# LionIRVT-TM4C_Main.net
KiCad netlist of a schematic drawn in Altium Designer
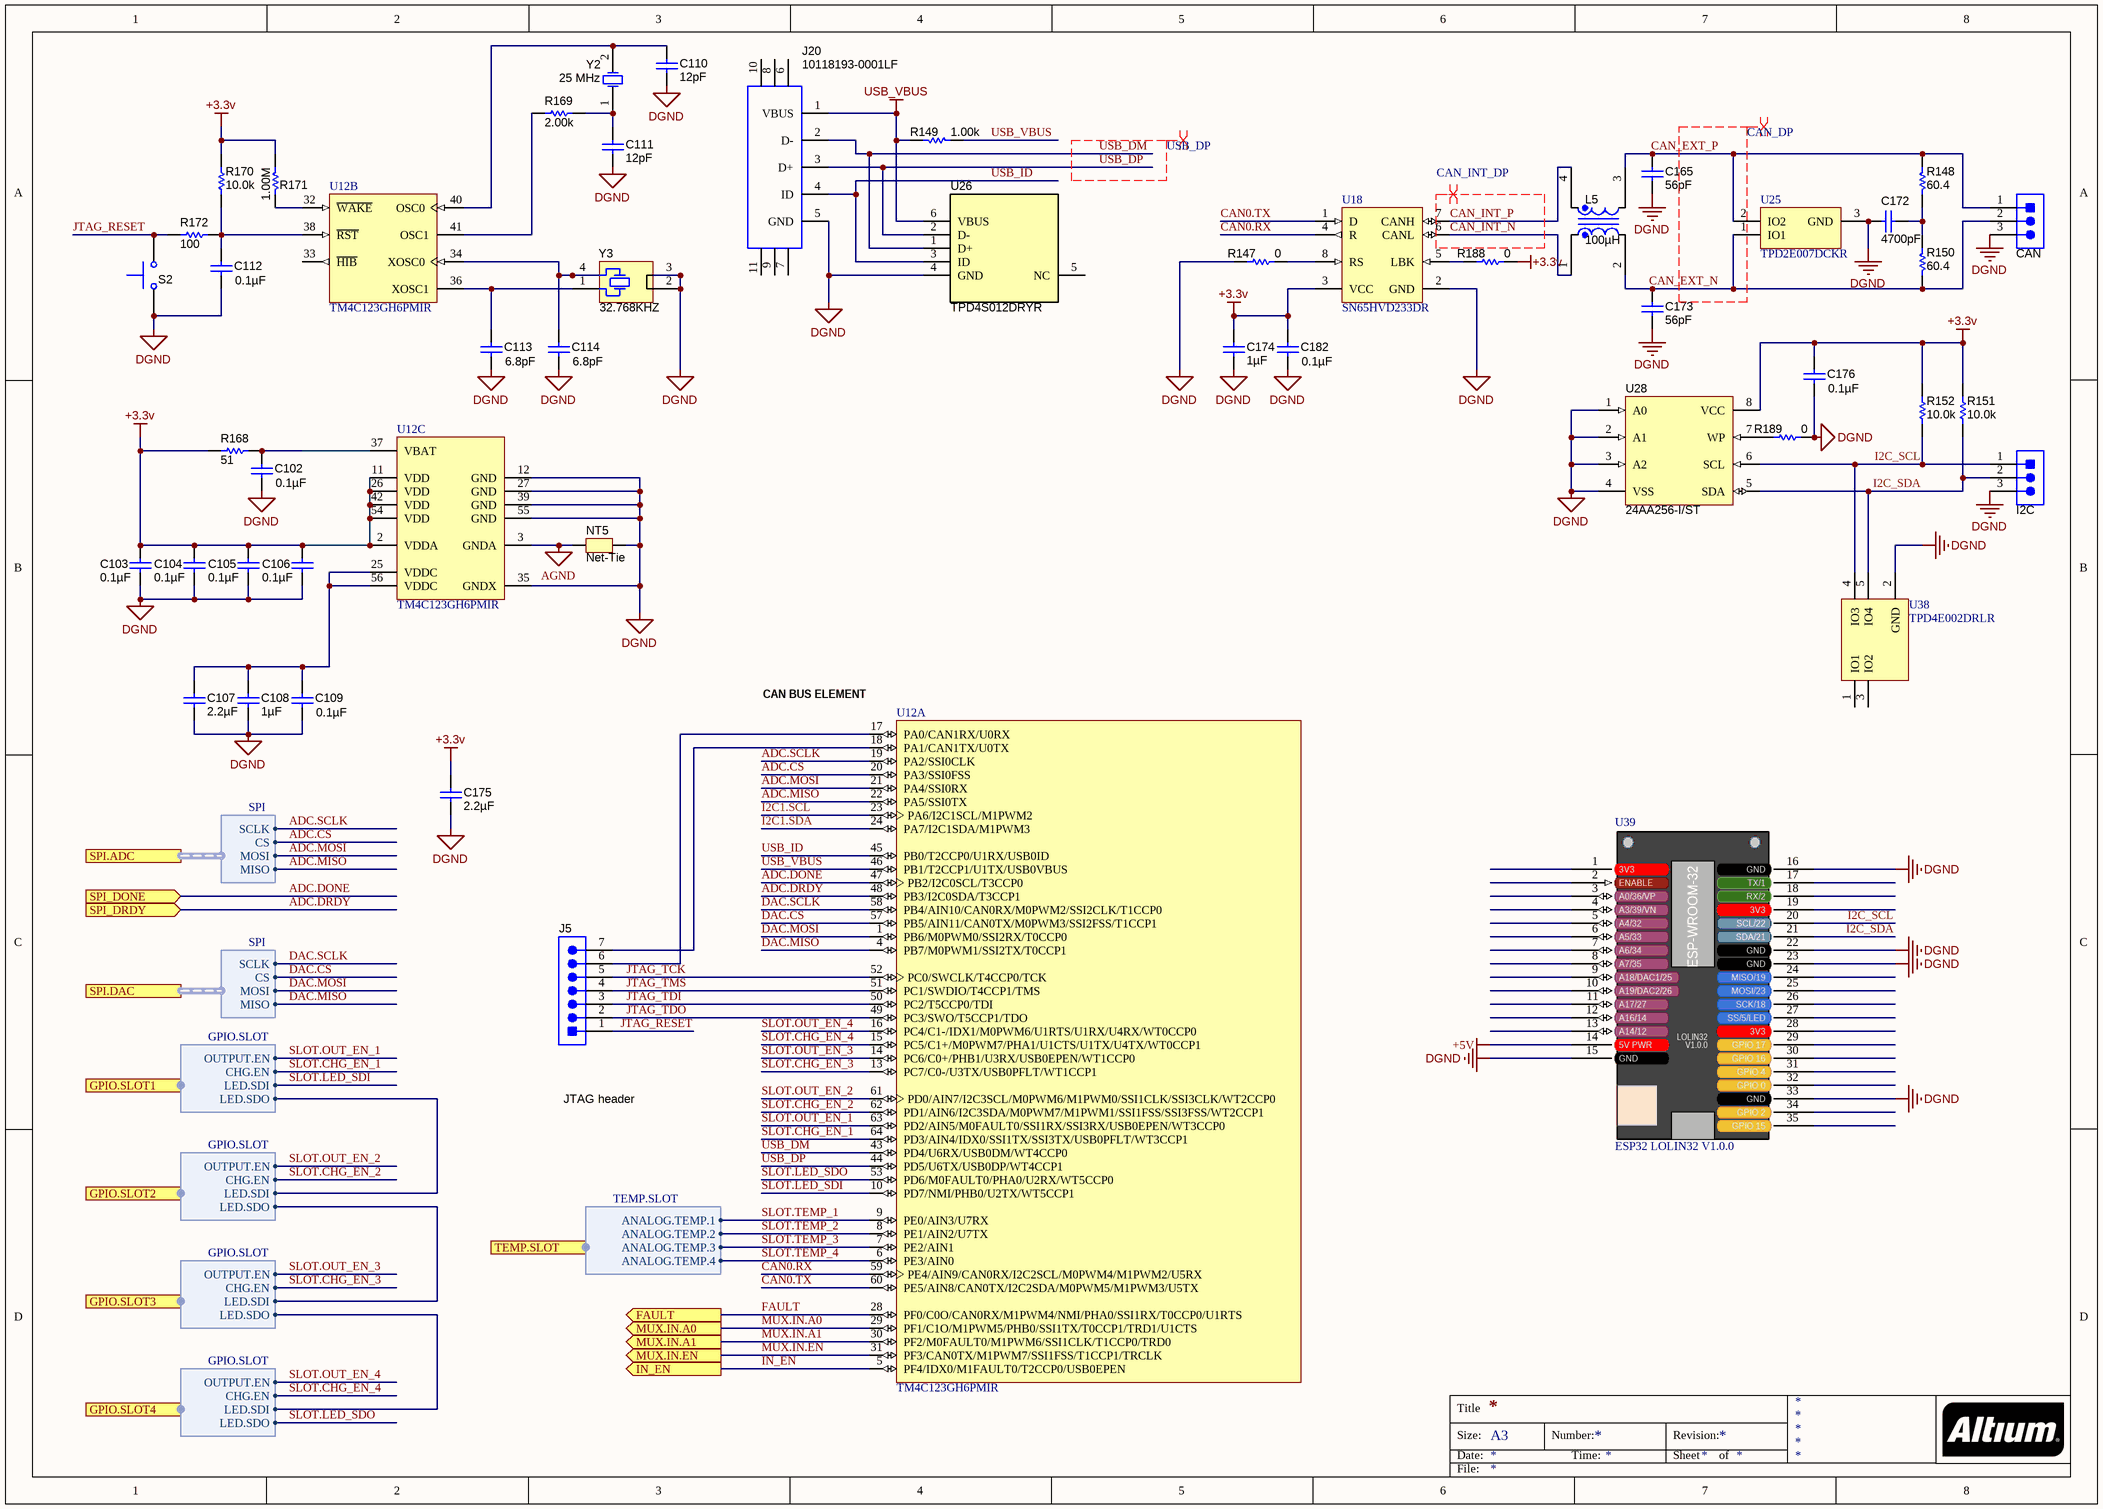
[diagram p0: LionIRVT-TM4C_Main.SchDoc]

(export (version "E")
  (design (tool "Eeschema 10.0.6"))
  (components
    (comp (ref "C102")
      (value "06033C104JAT2A")
      (footprint "0603C")
      (description "CAP, CERM, 0.1 µF, 25 V, +/- 5%, X7R, 0603")
      (fields
        (field (name "VALUEDISPLAYED") "0.1µF")
        (field (name "MANUFACTURER") "AVX")
        (field (name "PUBLISHER") "Texas Instruments")
      )
      (libsource (lib "Capacitor_Ceramic") (part "06033C104JAT2A"))
    )
    (comp (ref "C103")
      (value "06033C104JAT2A")
      (footprint "0603C")
      (description "CAP, CERM, 0.1 µF, 25 V, +/- 5%, X7R, 0603")
      (fields
        (field (name "VALUEDISPLAYED") "0.1µF")
        (field (name "MANUFACTURER") "AVX")
        (field (name "PUBLISHER") "Texas Instruments")
      )
      (libsource (lib "Capacitor_Ceramic") (part "06033C104JAT2A"))
    )
    (comp (ref "C104")
      (value "06033C104JAT2A")
      (footprint "0603C")
      (description "CAP, CERM, 0.1 µF, 25 V, +/- 5%, X7R, 0603")
      (fields
        (field (name "VALUEDISPLAYED") "0.1µF")
        (field (name "MANUFACTURER") "AVX")
        (field (name "PUBLISHER") "Texas Instruments")
      )
      (libsource (lib "Capacitor_Ceramic") (part "06033C104JAT2A"))
    )
    (comp (ref "C105")
      (value "06033C104JAT2A")
      (footprint "0603C")
      (description "CAP, CERM, 0.1 µF, 25 V, +/- 5%, X7R, 0603")
      (fields
        (field (name "VALUEDISPLAYED") "0.1µF")
        (field (name "MANUFACTURER") "AVX")
        (field (name "PUBLISHER") "Texas Instruments")
      )
      (libsource (lib "Capacitor_Ceramic") (part "06033C104JAT2A"))
    )
    (comp (ref "C106")
      (value "06033C104JAT2A")
      (footprint "0603C")
      (description "CAP, CERM, 0.1 µF, 25 V, +/- 5%, X7R, 0603")
      (fields
        (field (name "VALUEDISPLAYED") "0.1µF")
        (field (name "MANUFACTURER") "AVX")
        (field (name "PUBLISHER") "Texas Instruments")
      )
      (libsource (lib "Capacitor_Ceramic") (part "06033C104JAT2A"))
    )
    (comp (ref "C107")
      (value "GRM188R6YA225KA12D")
      (footprint "0603C")
      (description "CAP, CERM, 2.2 µF, 35 V, +/- 10%, X5R, 0603")
      (fields
        (field (name "VALUEDISPLAYED") "2.2µF")
        (field (name "MANUFACTURER") "MuRata")
        (field (name "PUBLISHER") "Texas Instruments")
      )
      (libsource (lib "Capacitor_Ceramic") (part "GRM188R6YA225KA12D"))
    )
    (comp (ref "C108")
      (value "GRM188R71E105KA12D")
      (footprint "0603C")
      (description "CAP, CERM, 1 µF, 25 V, +/- 10%, X7R, 0603")
      (fields
        (field (name "VALUEDISPLAYED") "1µF")
        (field (name "MANUFACTURER") "MuRata")
        (field (name "PUBLISHER") "Texas Instruments")
      )
      (libsource (lib "Capacitor_Ceramic") (part "GRM188R71E105KA12D"))
    )
    (comp (ref "C109")
      (value "06033C104JAT2A")
      (footprint "0603C")
      (description "CAP, CERM, 0.1 µF, 25 V, +/- 5%, X7R, 0603")
      (fields
        (field (name "VALUEDISPLAYED") "0.1µF")
        (field (name "MANUFACTURER") "AVX")
        (field (name "PUBLISHER") "Texas Instruments")
      )
      (libsource (lib "Capacitor_Ceramic") (part "06033C104JAT2A"))
    )
    (comp (ref "C110")
      (value "C0603C120J5GACTU")
      (footprint "0603C")
      (description "CAP, CERM, 12 pF, 50 V, +/- 5%, C0G/NP0, 0603")
      (fields
        (field (name "VALUEDISPLAYED") "12pF")
        (field (name "MANUFACTURER") "Kemet")
        (field (name "PUBLISHER") "Texas Instruments")
      )
      (libsource (lib "Capacitor_Ceramic") (part "C0603C120J5GACTU"))
    )
    (comp (ref "C111")
      (value "C0603C120J5GACTU")
      (footprint "0603C")
      (description "CAP, CERM, 12 pF, 50 V, +/- 5%, C0G/NP0, 0603")
      (fields
        (field (name "VALUEDISPLAYED") "12pF")
        (field (name "MANUFACTURER") "Kemet")
        (field (name "PUBLISHER") "Texas Instruments")
      )
      (libsource (lib "Capacitor_Ceramic") (part "C0603C120J5GACTU"))
    )
    (comp (ref "C112")
      (value "06033C104JAT2A")
      (footprint "0603C")
      (description "CAP, CERM, 0.1 µF, 25 V, +/- 5%, X7R, 0603")
      (fields
        (field (name "VALUEDISPLAYED") "0.1µF")
        (field (name "MANUFACTURER") "AVX")
        (field (name "PUBLISHER") "Texas Instruments")
      )
      (libsource (lib "Capacitor_Ceramic") (part "06033C104JAT2A"))
    )
    (comp (ref "C113")
      (value "06035A6R8CAT2A")
      (footprint "0603C")
      (description "CAP, CERM, 6.8 pF, 50 V, +/- 4%, C0G/NP0, 0603")
      (fields
        (field (name "VALUEDISPLAYED") "6.8pF")
        (field (name "MANUFACTURER") "AVX")
        (field (name "PUBLISHER") "Texas Instruments")
      )
      (libsource (lib "Capacitor_Ceramic") (part "06035A6R8CAT2A"))
    )
    (comp (ref "C114")
      (value "06035A6R8CAT2A")
      (footprint "0603C")
      (description "CAP, CERM, 6.8 pF, 50 V, +/- 4%, C0G/NP0, 0603")
      (fields
        (field (name "VALUEDISPLAYED") "6.8pF")
        (field (name "MANUFACTURER") "AVX")
        (field (name "PUBLISHER") "Texas Instruments")
      )
      (libsource (lib "Capacitor_Ceramic") (part "06035A6R8CAT2A"))
    )
    (comp (ref "C165")
      (value "GRM1885C1H560JA01D")
      (footprint "0603C")
      (description "CAP, CERM, 56 pF, 50 V, +/- 5%, C0G/NP0, 0603")
      (fields
        (field (name "VALUEDISPLAYED") "56pF")
        (field (name "MANUFACTURER") "MuRata")
        (field (name "PUBLISHER") "Texas Instruments")
      )
      (libsource (lib "Capacitor_Ceramic") (part "GRM1885C1H560JA01D"))
    )
    (comp (ref "C172")
      (value "GCM188R71H472KA37D")
      (footprint "0603C")
      (description "CAP, CERM, 4700 pF, 50 V, +/- 10%, X7R, AEC-Q200 Grade 1, 0603")
      (fields
        (field (name "VALUEDISPLAYED") "4700pF")
        (field (name "MANUFACTURER") "MuRata")
        (field (name "PUBLISHER") "Texas Instruments")
      )
      (libsource (lib "Capacitor_Ceramic") (part "GCM188R71H472KA37D"))
    )
    (comp (ref "C173")
      (value "GRM1885C1H560JA01D")
      (footprint "0603")
      (description "CAP, CERM, 56 pF, 50 V, +/- 5%, C0G/NP0, 0603")
      (fields
        (field (name "VALUEDISPLAYED") "56pF")
        (field (name "MANUFACTURER") "MuRata")
        (field (name "PUBLISHER") "Texas Instruments")
      )
      (libsource (lib "Capacitor_Ceramic") (part "GRM1885C1H560JA01D"))
    )
    (comp (ref "C174")
      (value "GRM188R71E105KA12D")
      (footprint "0603")
      (description "CAP, CERM, 1 µF, 25 V, +/- 10%, X7R, 0603")
      (fields
        (field (name "VALUEDISPLAYED") "1µF")
        (field (name "MANUFACTURER") "MuRata")
        (field (name "PUBLISHER") "Texas Instruments")
      )
      (libsource (lib "Capacitor_Ceramic") (part "GRM188R71E105KA12D"))
    )
    (comp (ref "C175")
      (value "GRM188R6YA225KA12D")
      (footprint "0603")
      (description "CAP, CERM, 2.2 µF, 35 V, +/- 10%, X5R, 0603")
      (fields
        (field (name "VALUEDISPLAYED") "2.2µF")
        (field (name "MANUFACTURER") "MuRata")
        (field (name "PUBLISHER") "Texas Instruments")
      )
      (libsource (lib "Capacitor_Ceramic") (part "GRM188R6YA225KA12D"))
    )
    (comp (ref "C176")
      (value "06033C104JAT2A")
      (footprint "0603C")
      (description "CAP, CERM, 0.1 µF, 25 V, +/- 5%, X7R, 0603")
      (fields
        (field (name "VALUEDISPLAYED") "0.1µF")
        (field (name "MANUFACTURER") "AVX")
        (field (name "PUBLISHER") "Texas Instruments")
      )
      (libsource (lib "Capacitor_Ceramic") (part "06033C104JAT2A"))
    )
    (comp (ref "C182")
      (value "06033C104JAT2A")
      (footprint "0603C")
      (description "CAP, CERM, 0.1 µF, 25 V, +/- 5%, X7R, 0603")
      (fields
        (field (name "VALUEDISPLAYED") "0.1µF")
        (field (name "MANUFACTURER") "AVX")
        (field (name "PUBLISHER") "Texas Instruments")
      )
      (libsource (lib "Capacitor_Ceramic") (part "06033C104JAT2A"))
    )
    (comp (ref "CAN")
      (value "ED555/3DS")
      (footprint "TERM_BLK_ED555-3DS")
      (description "Terminal Block, 6A, 3.5mm Pitch, 3-Pos, TH")
      (fields
        (field (name "MANUFACTURER") "On-Shore Technology")
        (field (name "SYMBOLCREATOR") "a0412235")
        (field (name "PUBLISHER") "Texas Instruments")
      )
      (libsource (lib "PWR578A") (part "ED555/3DS"))
    )
    (comp (ref "I2C")
      (value "ED555/3DS")
      (footprint "TERM_BLK_ED555-3DS")
      (description "Terminal Block, 6A, 3.5mm Pitch, 3-Pos, TH")
      (fields
        (field (name "MANUFACTURER") "On-Shore Technology")
        (field (name "SYMBOLCREATOR") "a0412235")
        (field (name "PUBLISHER") "Texas Instruments")
      )
      (libsource (lib "PWR578A") (part "ED555/3DS"))
    )
    (comp (ref "J5")
      (value "TSW-107-07-G-S")
      (footprint "TSW-107-07-G-S")
      (description "Header, 100mil, 7x1, Gold, TH")
      (fields
        (field (name "MANUFACTURER") "Samtec")
        (field (name "SYMBOLCREATOR") "a0411947")
        (field (name "PUBLISHER") "Texas Instruments")
      )
      (libsource (lib "Connectors_Samtec") (part "TSW-107-07-G-S"))
    )
    (comp (ref "J20")
      (value "10118193-0001LF")
      (footprint "FCI_10118193-0001LF")
      (description "Connector, Receptacle, USB Micro B, R/A, SMT")
      (fields (field (name "MANUFACTURER") "FCI") (field (name "PUBLISHER") "Texas Instruments"))
      (libsource (lib "SV601272A") (part "CMP-0065029-1"))
    )
    (comp (ref "L5")
      (value "B82789C0104H001")
      (footprint "SIMDAD_1812")
      (description "Coupled inductor, 100 µH, 0.15 A, 1.5 ohm, SMD")
      (fields
        (field (name "VALUEDISPLAYED") "100µH")
        (field (name "MANUFACTURER") "TDK")
        (field (name "SYMBOLCREATOR") "a0412235")
        (field (name "PUBLISHER") "Texas Instruments")
      )
      (libsource (lib "SV601272A") (part "B82789C0104H001"))
    )
    (comp (ref "NT5")
      (value "Net-Tie")
      (footprint "Net-Tie_10mil")
      (description "Single point connection between nets.")
      (fields (field (name "SYMBOLCREATOR") "codlsc") (field (name "PUBLISHER") "Texas Instruments"))
      (libsource (lib "SV601272A") (part "Net-Tie"))
    )
    (comp (ref "R147")
      (value "Resistor")
      (footprint "0603R")
      (description "RES, 0, 5%, 0.1 W, 0603")
      (fields
        (field (name "PARTNUMBER") "ERJ-3GEY0R00V")
        (field (name "MANUFACTURER") "Panasonic")
        (field (name "VALUEDISPLAYED") "0")
        (field (name "PUBLISHER") "Texas Instruments")
      )
      (libsource (lib "PMP40182") (part "Resistor"))
    )
    (comp (ref "R148")
      (value "CRCW120660R4FKEA")
      (footprint "1206R")
      (description "RES, 60.4, 1%, 0.25 W, 1206")
      (fields
        (field (name "VALUEDISPLAYED") "60.4")
        (field (name "MANUFACTURER") "Vishay-Dale")
        (field (name "PUBLISHER") "Texas Instruments")
      )
      (libsource (lib "Resistor_1206") (part "CRCW120660R4FKEA"))
    )
    (comp (ref "R149")
      (value "CRCW06031K00FKEA")
      (footprint "0603R")
      (description "RES, 1.00 k, 1%, 0.1 W, 0603")
      (fields
        (field (name "VALUEDISPLAYED") "1.00k")
        (field (name "MANUFACTURER") "Vishay-Dale")
        (field (name "PUBLISHER") "Texas Instruments")
      )
      (libsource (lib "Resistor_0603") (part "CRCW06031K00FKEA"))
    )
    (comp (ref "R150")
      (value "CRCW120660R4FKEA")
      (footprint "1206R")
      (description "RES, 60.4, 1%, 0.25 W, 1206")
      (fields
        (field (name "VALUEDISPLAYED") "60.4")
        (field (name "MANUFACTURER") "Vishay-Dale")
        (field (name "PUBLISHER") "Texas Instruments")
      )
      (libsource (lib "Resistor_1206") (part "CRCW120660R4FKEA"))
    )
    (comp (ref "R151")
      (value "CRCW060310K0FKEA")
      (footprint "0603R")
      (description "RES, 10.0 k, 1%, 0.1 W, 0603")
      (fields
        (field (name "VALUEDISPLAYED") "10.0k")
        (field (name "MANUFACTURER") "Vishay-Dale")
        (field (name "PUBLISHER") "Texas Instruments")
      )
      (libsource (lib "Resistor_0603") (part "CRCW060310K0FKEA"))
    )
    (comp (ref "R152")
      (value "CRCW060310K0FKEA")
      (footprint "0603R")
      (description "RES, 10.0 k, 1%, 0.1 W, 0603")
      (fields
        (field (name "VALUEDISPLAYED") "10.0k")
        (field (name "MANUFACTURER") "Vishay-Dale")
        (field (name "PUBLISHER") "Texas Instruments")
      )
      (libsource (lib "Resistor_0603") (part "CRCW060310K0FKEA"))
    )
    (comp (ref "R168")
      (value "CRCW060351R0JNEA")
      (footprint "0603R")
      (description "RES, 51, 5%, 0.1 W, 0603")
      (fields
        (field (name "VALUEDISPLAYED") "51")
        (field (name "MANUFACTURER") "Vishay-Dale")
        (field (name "PUBLISHER") "Texas Instruments")
      )
      (libsource (lib "Resistor_0603") (part "CRCW060351R0JNEA"))
    )
    (comp (ref "R169")
      (value "CRCW06032K00FKEA")
      (footprint "0603R")
      (description "RES, 2.00 k, 1%, 0.1 W, 0603")
      (fields
        (field (name "VALUEDISPLAYED") "2.00k")
        (field (name "MANUFACTURER") "Vishay-Dale")
        (field (name "PUBLISHER") "Texas Instruments")
      )
      (libsource (lib "Resistor_0603") (part "CRCW06032K00FKEA"))
    )
    (comp (ref "R170")
      (value "CRCW060310K0FKEA")
      (footprint "0603R")
      (description "RES, 10.0 k, 1%, 0.1 W, 0603")
      (fields
        (field (name "VALUEDISPLAYED") "10.0k")
        (field (name "MANUFACTURER") "Vishay-Dale")
        (field (name "PUBLISHER") "Texas Instruments")
      )
      (libsource (lib "Resistor_0603") (part "CRCW060310K0FKEA"))
    )
    (comp (ref "R171")
      (value "CRCW06031M00FKEA")
      (footprint "0603R")
      (description "RES, 1.00 M, 1%, 0.1 W, 0603")
      (fields
        (field (name "VALUEDISPLAYED") "1.00M")
        (field (name "MANUFACTURER") "Vishay-Dale")
        (field (name "PUBLISHER") "Texas Instruments")
      )
      (libsource (lib "Resistor_0603") (part "CRCW06031M00FKEA"))
    )
    (comp (ref "R172")
      (value "CRCW0603100RFKEA")
      (footprint "0603R")
      (description "RES, 100, 1%, 0.1 W, 0603")
      (fields
        (field (name "VALUEDISPLAYED") "100")
        (field (name "MANUFACTURER") "Vishay-Dale")
        (field (name "PUBLISHER") "Texas Instruments")
      )
      (libsource (lib "Resistor_0603") (part "CRCW0603100RFKEA"))
    )
    (comp (ref "R188")
      (value "Resistor")
      (footprint "0603R")
      (description "RES, 0, 5%, 0.1 W, 0603")
      (fields
        (field (name "PARTNUMBER") "ERJ-3GEY0R00V")
        (field (name "MANUFACTURER") "Panasonic")
        (field (name "VALUEDISPLAYED") "0")
        (field (name "PUBLISHER") "Texas Instruments")
      )
      (libsource (lib "PMP40182") (part "Resistor"))
    )
    (comp (ref "R189")
      (value "Resistor")
      (footprint "0603R")
      (description "RES, 0, 5%, 0.1 W, 0603")
      (fields
        (field (name "PARTNUMBER") "ERJ-3GEY0R00V")
        (field (name "MANUFACTURER") "Panasonic")
        (field (name "VALUEDISPLAYED") "0")
        (field (name "PUBLISHER") "Texas Instruments")
      )
      (libsource (lib "PMP40182") (part "Resistor"))
    )
    (comp (ref "S2")
      (value "TL1015AF160QG")
      (footprint "SW_TL1015AF160QG")
      (description "Switch, Tactile, SPST-NO, 0.05A, 12V, SMT")
      (fields
        (field (name "MANUFACTURER") "E-Switch")
        (field (name "SYMBOLCREATOR") "a0412235")
        (field (name "PUBLISHER") "Texas Instruments")
      )
      (libsource (lib "Switches") (part "TL1015AF160QG"))
    )
    (comp (ref "U12")
      (value "TM4C123GH6PMIR")
      (footprint "PM0064A_L")
      (fields (field (name "MANUFACTURER") "Texas Instruments"))
      (libsource (lib "Altium Content Vault") (part "TI-TM4C123GH6PM-LQFP-64"))
    )
    (comp (ref "U18")
      (value "SN65HVD233DR")
      (footprint "D0008A_M")
      (fields (field (name "MANUFACTURER") "Texas Instruments"))
      (libsource (lib "Altium Content Vault") (part "TI-SN65HVD233-SOIC_D-8"))
    )
    (comp (ref "U25")
      (value "TPD2E007DCKR")
      (footprint "DCK0003A_M")
      (fields (field (name "MANUFACTURER") "Texas Instruments"))
      (libsource (lib "Altium Content Vault") (part "TI-TPD2E007-SC70_DCK-3"))
    )
    (comp (ref "U26")
      (value "TPD4S012DRYR")
      (footprint "DRY0006A")
      (fields (field (name "MANUFACTURER") "Texas Instruments") (field (name "PARTNUMBER") "TPD4S012DRYR"))
      (libsource (lib "SV601272A") (part "CMP-0043122-2"))
    )
    (comp (ref "U28")
      (value "24AA256-I/ST")
      (footprint "TSSOP-8")
      (description "256K I2C™ CMOS Serial EEPROM, TSSOP-8")
      (fields
        (field (name "MANUFACTURER") "Microchip")
        (field (name "SYMBOLCREATOR") "a0411947")
        (field (name "PUBLISHER") "Texas Instruments")
      )
      (libsource (lib "Other_IC") (part "24AA256-I/ST"))
    )
    (comp (ref "U38")
      (value "TPD4E002DRLR")
      (footprint "DRL0005A_L")
      (fields (field (name "MANUFACTURER") "Texas Instruments"))
      (libsource (lib "Altium Content Vault") (part "TI-TPD4E002-SOT_DRL-5"))
    )
    (comp (ref "U39")
      (value "ESP32 LOLIN32 V1.0.0")
      (footprint "ESP32_LOLIN32_V1")
      (libsource (lib "Ir-Oven-Lib") (part "ESP32_WLOIN"))
    )
    (comp (ref "Y2")
      (value "ABM3-25.000MHZ-D2Y-T")
      (footprint "XTAL_ABM3")
      (description "Crystal, 25 MHz, 18 pF, SMD")
      (fields
        (field (name "FREQUENCY") "25 MHz")
        (field (name "MANUFACTURER") "Abracon Corportation")
        (field (name "SYMBOLCREATOR") "a0412235")
        (field (name "PUBLISHER") "Texas Instruments")
      )
      (libsource (lib "Oscillators") (part "ABM3-25.000MHZ-D2Y-T"))
    )
    (comp (ref "Y3")
      (value "SSPT7F-7PF20-R")
      (footprint "Seiko_SSP-T")
      (description "CRYSTAL, 32.768KHZ, 7PF, SMD")
      (fields
        (field (name "FREQUENCY") "32.768KHZ")
        (field (name "MANUFACTURER") "Seiko Instruments")
        (field (name "SYMBOLCREATOR") "x0208325")
        (field (name "PUBLISHER") "Texas Instruments")
      )
      (libsource (lib "Oscillators") (part "SSPT7F-7PF20-R"))
    )
  )
  (nets
    (net (code "4") (name "+3.3v") (class "Default")
      (node (ref "C103") (pin "2") (pinfunction "2_2") (pintype "passive"))
      (node (ref "C104") (pin "2") (pinfunction "2_2") (pintype "passive"))
      (node (ref "C105") (pin "2") (pinfunction "2_2") (pintype "passive"))
      (node (ref "C106") (pin "2") (pinfunction "2_2") (pintype "passive"))
      (node (ref "C174") (pin "1") (pinfunction "1_1") (pintype "passive"))
      (node (ref "C175") (pin "1") (pinfunction "1_1") (pintype "passive"))
      (node (ref "C176") (pin "2") (pinfunction "2_2") (pintype "passive"))
      (node (ref "C182") (pin "2") (pinfunction "2_2") (pintype "passive"))
      (node (ref "R151") (pin "2") (pinfunction "2_2") (pintype "passive"))
      (node (ref "R152") (pin "2") (pinfunction "2_2") (pintype "passive"))
      (node (ref "R168") (pin "1") (pinfunction "1_1") (pintype "passive"))
      (node (ref "R170") (pin "2") (pinfunction "2_2") (pintype "passive"))
      (node (ref "R171") (pin "2") (pinfunction "2_2") (pintype "passive"))
      (node (ref "R188") (pin "2") (pinfunction "2_2") (pintype "passive"))
      (node (ref "U12") (pin "11") (pinfunction "VDD_11") (pintype "power_in"))
      (node (ref "U12") (pin "2") (pinfunction "VDDA_2") (pintype "power_in"))
      (node (ref "U12") (pin "26") (pinfunction "VDD_26") (pintype "power_in"))
      (node (ref "U12") (pin "42") (pinfunction "VDD_42") (pintype "power_in"))
      (node (ref "U12") (pin "54") (pinfunction "VDD_54") (pintype "power_in"))
      (node (ref "U18") (pin "3") (pinfunction "VCC_3") (pintype "power_in"))
      (node (ref "U28") (pin "8") (pinfunction "VCC_8") (pintype "power_in"))
    )
    (net (code "5") (name "+5V") (class "Default")
      (node (ref "U39") (pin "14") (pinfunction "5V_PWR_14") (pintype "power_in"))
    )
    (net (code "6") (name "/ADC.CS") (class "Default")
      (node (ref "U12") (pin "20") (pinfunction "PA3/SSI0FSS_20") (pintype "bidirectional"))
    )
    (net (code "7") (name "/ADC.DONE") (class "Default")
      (node (ref "U12") (pin "47") (pinfunction "PB2/I2C0SCL/T3CCP0_47") (pintype "bidirectional"))
    )
    (net (code "8") (name "/ADC.DRDY") (class "Default")
      (node (ref "U12") (pin "48") (pinfunction "PB3/I2C0SDA/T3CCP1_48") (pintype "bidirectional"))
    )
    (net (code "9") (name "/ADC.MISO") (class "Default")
      (node (ref "U12") (pin "22") (pinfunction "PA5/SSI0TX_22") (pintype "bidirectional"))
    )
    (net (code "10") (name "/ADC.MOSI") (class "Default")
      (node (ref "U12") (pin "21") (pinfunction "PA4/SSI0RX_21") (pintype "bidirectional"))
    )
    (net (code "11") (name "/ADC.SCLK") (class "Default")
      (node (ref "U12") (pin "19") (pinfunction "PA2/SSI0CLK_19") (pintype "bidirectional"))
    )
    (net (code "12") (name "/CAN0.RX") (class "Default")
      (node (ref "U12") (pin "59") (pinfunction "PE4/AIN9/CAN0RX/I2C2SCL/M0PWM4/M1PWM2/U5RX_59") (pintype "bidirectional"))
      (node (ref "U18") (pin "4") (pinfunction "R_4") (pintype "output"))
    )
    (net (code "13") (name "/CAN0.TX") (class "Default")
      (node (ref "U12") (pin "60") (pinfunction "PE5/AIN8/CAN0TX/I2C2SDA/M0PWM5/M1PWM3/U5TX_60") (pintype "bidirectional"))
      (node (ref "U18") (pin "1") (pinfunction "D_1") (pintype "input"))
    )
    (net (code "14") (name "/CAN_EXT_N") (class "Default")
      (node (ref "C173") (pin "1") (pinfunction "1_1") (pintype "passive"))
      (node (ref "CAN") (pin "2") (pinfunction "2_2") (pintype "passive"))
      (node (ref "L5") (pin "2") (pinfunction "2_2") (pintype "passive"))
      (node (ref "R150") (pin "1") (pinfunction "1_1") (pintype "passive"))
      (node (ref "U25") (pin "1") (pinfunction "IO1_1") (pintype "passive"))
    )
    (net (code "15") (name "/CAN_EXT_P") (class "Default")
      (node (ref "C165") (pin "1") (pinfunction "1_1") (pintype "passive"))
      (node (ref "CAN") (pin "1") (pinfunction "1_1") (pintype "passive"))
      (node (ref "L5") (pin "3") (pinfunction "3_3") (pintype "passive"))
      (node (ref "R148") (pin "2") (pinfunction "2_2") (pintype "passive"))
      (node (ref "U25") (pin "2") (pinfunction "IO2_2") (pintype "passive"))
    )
    (net (code "16") (name "/CAN_INT_N") (class "Default")
      (node (ref "L5") (pin "1") (pinfunction "1_1") (pintype "passive"))
      (node (ref "U18") (pin "6") (pinfunction "CANL_6") (pintype "bidirectional"))
    )
    (net (code "17") (name "/CAN_INT_P") (class "Default")
      (node (ref "L5") (pin "4") (pinfunction "4_4") (pintype "passive"))
      (node (ref "U18") (pin "7") (pinfunction "CANH_7") (pintype "bidirectional"))
    )
    (net (code "18") (name "/DAC.CS") (class "Default")
      (node (ref "U12") (pin "57") (pinfunction "PB5/AIN11/CAN0TX/M0PWM3/SSI2FSS/T1CCP1_57") (pintype "bidirectional"))
    )
    (net (code "19") (name "/DAC.MISO") (class "Default")
      (node (ref "U12") (pin "4") (pinfunction "PB7/M0PWM1/SSI2TX/T0CCP1_4") (pintype "bidirectional"))
    )
    (net (code "20") (name "/DAC.MOSI") (class "Default")
      (node (ref "U12") (pin "1") (pinfunction "PB6/M0PWM0/SSI2RX/T0CCP0_1") (pintype "bidirectional"))
    )
    (net (code "21") (name "/DAC.SCLK") (class "Default")
      (node (ref "U12") (pin "58") (pinfunction "PB4/AIN10/CAN0RX/M0PWM2/SSI2CLK/T1CCP0_58") (pintype "bidirectional"))
    )
    (net (code "22") (name "/FAULT") (class "Default")
      (node (ref "U12") (pin "28") (pinfunction "PF0/C0O/CAN0RX/M1PWM4/NMI/PHA0/SSI1RX/T0CCP0/U1RTS_28") (pintype "bidirectional"))
    )
    (net (code "23") (name "/I2C1.SCL") (class "Default")
      (node (ref "U12") (pin "23") (pinfunction "PA6/I2C1SCL/M1PWM2_23") (pintype "bidirectional"))
    )
    (net (code "24") (name "/I2C1.SDA") (class "Default")
      (node (ref "U12") (pin "24") (pinfunction "PA7/I2C1SDA/M1PWM3_24") (pintype "bidirectional"))
    )
    (net (code "25") (name "/I2C_SCL") (class "Default")
      (node (ref "I2C") (pin "1") (pinfunction "1_1") (pintype "passive"))
      (node (ref "R152") (pin "1") (pinfunction "1_1") (pintype "passive"))
      (node (ref "U28") (pin "6") (pinfunction "SCL_6") (pintype "input"))
      (node (ref "U38") (pin "4") (pinfunction "IO3_4") (pintype "passive"))
      (node (ref "U39") (pin "20") (pinfunction "SCL/22_20") (pintype "power_in"))
    )
    (net (code "26") (name "/I2C_SDA") (class "Default")
      (node (ref "I2C") (pin "2") (pinfunction "2_2") (pintype "passive"))
      (node (ref "R151") (pin "1") (pinfunction "1_1") (pintype "passive"))
      (node (ref "U28") (pin "5") (pinfunction "SDA_5") (pintype "bidirectional"))
      (node (ref "U38") (pin "5") (pinfunction "IO4_5") (pintype "passive"))
      (node (ref "U39") (pin "21") (pinfunction "SDA/21_21") (pintype "power_in"))
    )
    (net (code "27") (name "/IN_EN") (class "Default")
      (node (ref "U12") (pin "5") (pinfunction "PF4/IDX0/M1FAULT0/T2CCP0/USB0EPEN_5") (pintype "bidirectional"))
    )
    (net (code "28") (name "/JTAG_RESET") (class "Default")
      (node (ref "J5") (pin "1") (pinfunction "1_1") (pintype "passive"))
      (node (ref "R172") (pin "1") (pinfunction "1_1") (pintype "passive"))
      (node (ref "S2") (pin "2") (pinfunction "2_2") (pintype "passive"))
    )
    (net (code "29") (name "/JTAG_TCK") (class "Default")
      (node (ref "J5") (pin "5") (pinfunction "5_5") (pintype "passive"))
      (node (ref "U12") (pin "52") (pinfunction "PC0/SWCLK/T4CCP0/TCK_52") (pintype "bidirectional"))
    )
    (net (code "30") (name "/JTAG_TDI") (class "Default")
      (node (ref "J5") (pin "3") (pinfunction "3_3") (pintype "passive"))
      (node (ref "U12") (pin "50") (pinfunction "PC2/T5CCP0/TDI_50") (pintype "bidirectional"))
    )
    (net (code "31") (name "/JTAG_TDO") (class "Default")
      (node (ref "J5") (pin "2") (pinfunction "2_2") (pintype "passive"))
      (node (ref "U12") (pin "49") (pinfunction "PC3/SWO/T5CCP1/TDO_49") (pintype "bidirectional"))
    )
    (net (code "32") (name "/JTAG_TMS") (class "Default")
      (node (ref "J5") (pin "4") (pinfunction "4_4") (pintype "passive"))
      (node (ref "U12") (pin "51") (pinfunction "PC1/SWDIO/T4CCP1/TMS_51") (pintype "bidirectional"))
    )
    (net (code "33") (name "/MUX.IN.A0") (class "Default")
      (node (ref "U12") (pin "29") (pinfunction "PF1/C1O/M1PWM5/PHB0/SSI1TX/T0CCP1/TRD1/U1CTS_29") (pintype "bidirectional"))
    )
    (net (code "34") (name "/MUX.IN.A1") (class "Default")
      (node (ref "U12") (pin "30") (pinfunction "PF2/M0FAULT0/M1PWM6/SSI1CLK/T1CCP0/TRD0_30") (pintype "bidirectional"))
    )
    (net (code "35") (name "/MUX.IN.EN") (class "Default")
      (node (ref "U12") (pin "31") (pinfunction "PF3/CAN0TX/M1PWM7/SSI1FSS/T1CCP1/TRCLK_31") (pintype "bidirectional"))
    )
    (net (code "36") (name "/SLOT.CHG_EN_1") (class "Default")
      (node (ref "U12") (pin "64") (pinfunction "PD3/AIN4/IDX0/SSI1TX/SSI3TX/USB0PFLT/WT3CCP1_64") (pintype "bidirectional"))
    )
    (net (code "37") (name "/SLOT.CHG_EN_2") (class "Default")
      (node (ref "U12") (pin "62") (pinfunction "PD1/AIN6/I2C3SDA/M0PWM7/M1PWM1/SSI1FSS/SSI3FSS/WT2CCP1_62") (pintype "bidirectional"))
    )
    (net (code "38") (name "/SLOT.CHG_EN_3") (class "Default")
      (node (ref "U12") (pin "13") (pinfunction "PC7/C0-/U3TX/USB0PFLT/WT1CCP1_13") (pintype "bidirectional"))
    )
    (net (code "39") (name "/SLOT.CHG_EN_4") (class "Default")
      (node (ref "U12") (pin "15") (pinfunction "PC5/C1+/M0PWM7/PHA1/U1CTS/U1TX/U4TX/WT0CCP1_15") (pintype "bidirectional"))
    )
    (net (code "40") (name "/SLOT.LED_SDI") (class "Default")
      (node (ref "U12") (pin "10") (pinfunction "PD7/NMI/PHB0/U2TX/WT5CCP1_10") (pintype "bidirectional"))
    )
    (net (code "41") (name "/SLOT.LED_SDO") (class "Default")
      (node (ref "U12") (pin "53") (pinfunction "PD6/M0FAULT0/PHA0/U2RX/WT5CCP0_53") (pintype "bidirectional"))
    )
    (net (code "42") (name "/SLOT.OUT_EN_1") (class "Default")
      (node (ref "U12") (pin "63") (pinfunction "PD2/AIN5/M0FAULT0/SSI1RX/SSI3RX/USB0EPEN/WT3CCP0_63") (pintype "bidirectional"))
    )
    (net (code "43") (name "/SLOT.OUT_EN_2") (class "Default")
      (node (ref "U12") (pin "61") (pinfunction "PD0/AIN7/I2C3SCL/M0PWM6/M1PWM0/SSI1CLK/SSI3CLK/WT2CCP0_61") (pintype "bidirectional"))
    )
    (net (code "44") (name "/SLOT.OUT_EN_3") (class "Default")
      (node (ref "U12") (pin "14") (pinfunction "PC6/C0+/PHB1/U3RX/USB0EPEN/WT1CCP0_14") (pintype "bidirectional"))
    )
    (net (code "45") (name "/SLOT.OUT_EN_4") (class "Default")
      (node (ref "U12") (pin "16") (pinfunction "PC4/C1-/IDX1/M0PWM6/U1RTS/U1RX/U4RX/WT0CCP0_16") (pintype "bidirectional"))
    )
    (net (code "46") (name "/SLOT.TEMP_1") (class "Default")
      (node (ref "U12") (pin "9") (pinfunction "PE0/AIN3/U7RX_9") (pintype "bidirectional"))
    )
    (net (code "47") (name "/SLOT.TEMP_2") (class "Default")
      (node (ref "U12") (pin "8") (pinfunction "PE1/AIN2/U7TX_8") (pintype "bidirectional"))
    )
    (net (code "48") (name "/SLOT.TEMP_3") (class "Default")
      (node (ref "U12") (pin "7") (pinfunction "PE2/AIN1_7") (pintype "bidirectional"))
    )
    (net (code "49") (name "/SLOT.TEMP_4") (class "Default")
      (node (ref "U12") (pin "6") (pinfunction "PE3/AIN0_6") (pintype "bidirectional"))
    )
    (net (code "50") (name "/USB_DM") (class "Default")
      (node (ref "J20") (pin "2") (pinfunction "D-_2") (pintype "passive"))
      (node (ref "U12") (pin "43") (pinfunction "PD4/U6RX/USB0DM/WT4CCP0_43") (pintype "bidirectional"))
      (node (ref "U26") (pin "1") (pinfunction "D+_1") (pintype "passive"))
    )
    (net (code "51") (name "/USB_DP") (class "Default")
      (node (ref "J20") (pin "3") (pinfunction "D+_3") (pintype "passive"))
      (node (ref "U12") (pin "44") (pinfunction "PD5/U6TX/USB0DP/WT4CCP1_44") (pintype "bidirectional"))
      (node (ref "U26") (pin "2") (pinfunction "D-_2") (pintype "passive"))
    )
    (net (code "52") (name "/USB_ID") (class "Default")
      (node (ref "J20") (pin "4") (pinfunction "ID_4") (pintype "passive"))
      (node (ref "U12") (pin "45") (pinfunction "PB0/T2CCP0/U1RX/USB0ID_45") (pintype "bidirectional"))
      (node (ref "U26") (pin "3") (pinfunction "ID_3") (pintype "passive"))
    )
    (net (code "56") (name "AGND") (class "Default")
      (node (ref "NT5") (pin "1") (pinfunction "1_1") (pintype "passive"))
      (node (ref "U12") (pin "3") (pinfunction "GNDA_3") (pintype "power_in"))
    )
    (net (code "57") (name "DGND") (class "Default")
      (node (ref "C102") (pin "1") (pinfunction "1_1") (pintype "passive"))
      (node (ref "C103") (pin "1") (pinfunction "1_1") (pintype "passive"))
      (node (ref "C104") (pin "1") (pinfunction "1_1") (pintype "passive"))
      (node (ref "C105") (pin "1") (pinfunction "1_1") (pintype "passive"))
      (node (ref "C106") (pin "1") (pinfunction "1_1") (pintype "passive"))
      (node (ref "C107") (pin "2") (pinfunction "2_2") (pintype "passive"))
      (node (ref "C108") (pin "2") (pinfunction "2_2") (pintype "passive"))
      (node (ref "C109") (pin "1") (pinfunction "1_1") (pintype "passive"))
      (node (ref "C110") (pin "2") (pinfunction "2_2") (pintype "passive"))
      (node (ref "C111") (pin "2") (pinfunction "2_2") (pintype "passive"))
      (node (ref "C112") (pin "1") (pinfunction "1_1") (pintype "passive"))
      (node (ref "C113") (pin "1") (pinfunction "1_1") (pintype "passive"))
      (node (ref "C114") (pin "1") (pinfunction "1_1") (pintype "passive"))
      (node (ref "C165") (pin "2") (pinfunction "2_2") (pintype "passive"))
      (node (ref "C172") (pin "1") (pinfunction "1_1") (pintype "passive"))
      (node (ref "C173") (pin "2") (pinfunction "2_2") (pintype "passive"))
      (node (ref "C174") (pin "2") (pinfunction "2_2") (pintype "passive"))
      (node (ref "C175") (pin "2") (pinfunction "2_2") (pintype "passive"))
      (node (ref "C176") (pin "1") (pinfunction "1_1") (pintype "passive"))
      (node (ref "C182") (pin "1") (pinfunction "1_1") (pintype "passive"))
      (node (ref "CAN") (pin "3") (pinfunction "3_3") (pintype "passive"))
      (node (ref "I2C") (pin "3") (pinfunction "3_3") (pintype "passive"))
      (node (ref "J20") (pin "5") (pinfunction "GND_5") (pintype "passive"))
      (node (ref "NT5") (pin "2") (pinfunction "2_2") (pintype "passive"))
      (node (ref "R147") (pin "1") (pinfunction "1_1") (pintype "passive"))
      (node (ref "R189") (pin "2") (pinfunction "2_2") (pintype "passive"))
      (node (ref "S2") (pin "1") (pinfunction "1_1") (pintype "passive"))
      (node (ref "U12") (pin "12") (pinfunction "GND_12") (pintype "power_in"))
      (node (ref "U12") (pin "27") (pinfunction "GND_27") (pintype "power_in"))
      (node (ref "U12") (pin "35") (pinfunction "GNDX_35") (pintype "power_in"))
      (node (ref "U12") (pin "39") (pinfunction "GND_39") (pintype "power_in"))
      (node (ref "U12") (pin "55") (pinfunction "GND_55") (pintype "power_in"))
      (node (ref "U18") (pin "2") (pinfunction "GND_2") (pintype "power_in"))
      (node (ref "U25") (pin "3") (pinfunction "GND_3") (pintype "power_in"))
      (node (ref "U26") (pin "4") (pinfunction "GND_4") (pintype "power_in"))
      (node (ref "U28") (pin "1") (pinfunction "A0_1") (pintype "input"))
      (node (ref "U28") (pin "2") (pinfunction "A1_2") (pintype "input"))
      (node (ref "U28") (pin "3") (pinfunction "A2_3") (pintype "input"))
      (node (ref "U28") (pin "4") (pinfunction "VSS_4") (pintype "power_in"))
      (node (ref "U38") (pin "2") (pinfunction "GND_2") (pintype "power_in"))
      (node (ref "U39") (pin "15") (pinfunction "GND_15") (pintype "power_in"))
      (node (ref "U39") (pin "16") (pinfunction "GND_16") (pintype "power_in"))
      (node (ref "U39") (pin "22") (pinfunction "GND_22") (pintype "power_in"))
      (node (ref "U39") (pin "23") (pinfunction "GND_23") (pintype "power_in"))
      (node (ref "U39") (pin "33") (pinfunction "GND_33") (pintype "power_in"))
      (node (ref "Y3") (pin "2") (pinfunction "2_2") (pintype "passive"))
      (node (ref "Y3") (pin "3") (pinfunction "3_3") (pintype "passive"))
    )
    (net (code "58") (name "Net-(C107-Pad1)") (class "Default")
      (node (ref "C107") (pin "1") (pinfunction "1_1") (pintype "passive"))
      (node (ref "C108") (pin "1") (pinfunction "1_1") (pintype "passive"))
      (node (ref "C109") (pin "2") (pinfunction "2_2") (pintype "passive"))
      (node (ref "U12") (pin "25") (pinfunction "VDDC_25") (pintype "power_in"))
      (node (ref "U12") (pin "56") (pinfunction "VDDC_56") (pintype "power_in"))
    )
    (net (code "59") (name "Net-(C172-Pad2)") (class "Default")
      (node (ref "C172") (pin "2") (pinfunction "2_2") (pintype "passive"))
      (node (ref "R148") (pin "1") (pinfunction "1_1") (pintype "passive"))
      (node (ref "R150") (pin "2") (pinfunction "2_2") (pintype "passive"))
    )
    (net (code "60") (name "Net-(U12A-PA0{slash}CAN1RX{slash}U0RX)") (class "Default")
      (node (ref "J5") (pin "6") (pinfunction "6_6") (pintype "passive"))
      (node (ref "U12") (pin "17") (pinfunction "PA0/CAN1RX/U0RX_17") (pintype "bidirectional"))
    )
    (net (code "61") (name "Net-(U12A-PA1{slash}CAN1TX{slash}U0TX)") (class "Default")
      (node (ref "J5") (pin "7") (pinfunction "7_7") (pintype "passive"))
      (node (ref "U12") (pin "18") (pinfunction "PA1/CAN1TX/U0TX_18") (pintype "bidirectional"))
    )
    (net (code "62") (name "Net-(U12B-OSC0)") (class "Default")
      (node (ref "C110") (pin "1") (pinfunction "1_1") (pintype "passive"))
      (node (ref "U12") (pin "40") (pinfunction "OSC0_40") (pintype "input"))
      (node (ref "Y2") (pin "2") (pinfunction "OSC2_2") (pintype "passive"))
    )
    (net (code "63") (name "Net-(U12B-OSC1)") (class "Default")
      (node (ref "R169") (pin "2") (pinfunction "2_2") (pintype "passive"))
      (node (ref "U12") (pin "41") (pinfunction "OSC1_41") (pintype "passive"))
    )
    (net (code "64") (name "Net-(U12B-XOSC0)") (class "Default")
      (node (ref "C114") (pin "2") (pinfunction "2_2") (pintype "passive"))
      (node (ref "U12") (pin "34") (pinfunction "XOSC0_34") (pintype "input"))
      (node (ref "Y3") (pin "4") (pinfunction "4_4") (pintype "passive"))
    )
    (net (code "65") (name "Net-(U12B-XOSC1)") (class "Default")
      (node (ref "C113") (pin "2") (pinfunction "2_2") (pintype "passive"))
      (node (ref "U12") (pin "36") (pinfunction "XOSC1_36") (pintype "passive"))
      (node (ref "Y3") (pin "1") (pinfunction "1_1") (pintype "passive"))
    )
    (net (code "66") (name "Net-(U12B-~{RST})") (class "Default")
      (node (ref "C112") (pin "2") (pinfunction "2_2") (pintype "passive"))
      (node (ref "R170") (pin "1") (pinfunction "1_1") (pintype "passive"))
      (node (ref "R172") (pin "2") (pinfunction "2_2") (pintype "passive"))
      (node (ref "U12") (pin "38") (pinfunction "~{RST}_38") (pintype "input"))
    )
    (net (code "67") (name "Net-(U12B-~{WAKE})") (class "Default")
      (node (ref "R171") (pin "1") (pinfunction "1_1") (pintype "passive"))
      (node (ref "U12") (pin "32") (pinfunction "~{WAKE}_32") (pintype "input"))
    )
    (net (code "68") (name "Net-(U12C-VBAT)") (class "Default")
      (node (ref "C102") (pin "2") (pinfunction "2_2") (pintype "passive"))
      (node (ref "R168") (pin "2") (pinfunction "2_2") (pintype "passive"))
      (node (ref "U12") (pin "37") (pinfunction "VBAT_37") (pintype "power_in"))
    )
    (net (code "69") (name "Net-(U18-LBK)") (class "Default")
      (node (ref "R188") (pin "1") (pinfunction "1_1") (pintype "passive"))
      (node (ref "U18") (pin "5") (pinfunction "LBK_5") (pintype "input"))
    )
    (net (code "70") (name "Net-(U18-RS)") (class "Default")
      (node (ref "R147") (pin "2") (pinfunction "2_2") (pintype "passive"))
      (node (ref "U18") (pin "8") (pinfunction "RS_8") (pintype "input"))
    )
    (net (code "71") (name "Net-(U28-WP)") (class "Default")
      (node (ref "R189") (pin "1") (pinfunction "1_1") (pintype "passive"))
      (node (ref "U28") (pin "7") (pinfunction "WP_7") (pintype "input"))
    )
    (net (code "72") (name "Net-(Y2-OSC1)") (class "Default")
      (node (ref "C111") (pin "1") (pinfunction "1_1") (pintype "passive"))
      (node (ref "R169") (pin "1") (pinfunction "1_1") (pintype "passive"))
      (node (ref "Y2") (pin "1") (pinfunction "OSC1_1") (pintype "passive"))
    )
    (net (code "73") (name "USB_VBUS") (class "Default")
      (node (ref "J20") (pin "1") (pinfunction "VBUS_1") (pintype "passive"))
      (node (ref "R149") (pin "1") (pinfunction "1_1") (pintype "passive"))
      (node (ref "R149") (pin "2") (pinfunction "2_2") (pintype "passive"))
      (node (ref "U12") (pin "46") (pinfunction "PB1/T2CCP1/U1TX/USB0VBUS_46") (pintype "bidirectional"))
      (node (ref "U26") (pin "6") (pinfunction "VBUS_6") (pintype "passive"))
    )
    (net (code "74") (name "unconnected-(J20-Pad6)") (class "Default")
      (node (ref "J20") (pin "6") (pinfunction "6_6") (pintype "passive"))
    )
    (net (code "75") (name "unconnected-(J20-Pad7)") (class "Default")
      (node (ref "J20") (pin "7") (pinfunction "7_7") (pintype "passive"))
    )
    (net (code "76") (name "unconnected-(J20-Pad8)") (class "Default")
      (node (ref "J20") (pin "8") (pinfunction "8_8") (pintype "passive"))
    )
    (net (code "77") (name "unconnected-(J20-Pad9)") (class "Default")
      (node (ref "J20") (pin "9") (pinfunction "9_9") (pintype "passive"))
    )
    (net (code "78") (name "unconnected-(J20-Pad10)") (class "Default")
      (node (ref "J20") (pin "10") (pinfunction "10_10") (pintype "passive"))
    )
    (net (code "79") (name "unconnected-(J20-Pad11)") (class "Default")
      (node (ref "J20") (pin "11") (pinfunction "11_11") (pintype "passive"))
    )
    (net (code "80") (name "unconnected-(U12B-~{HIB}-Pad33)") (class "Default")
      (node (ref "U12") (pin "33") (pinfunction "~{HIB}_33") (pintype "output"))
    )
    (net (code "81") (name "unconnected-(U26-NC-Pad5)") (class "Default")
      (node (ref "U26") (pin "5") (pinfunction "NC_5") (pintype "passive"))
    )
    (net (code "82") (name "unconnected-(U38-IO1-Pad1)") (class "Default")
      (node (ref "U38") (pin "1") (pinfunction "IO1_1") (pintype "passive"))
    )
    (net (code "83") (name "unconnected-(U38-IO2-Pad3)") (class "Default")
      (node (ref "U38") (pin "3") (pinfunction "IO2_3") (pintype "passive"))
    )
    (net (code "84") (name "unconnected-(U39-3V3-Pad1)") (class "Default")
      (node (ref "U39") (pin "1") (pinfunction "3V3_1") (pintype "power_in"))
    )
    (net (code "85") (name "unconnected-(U39-3V3-Pad19)") (class "Default")
      (node (ref "U39") (pin "19") (pinfunction "3V3_19") (pintype "power_in"))
    )
    (net (code "86") (name "unconnected-(U39-3V3-Pad28)") (class "Default")
      (node (ref "U39") (pin "28") (pinfunction "3V3_28") (pintype "power_in"))
    )
    (net (code "87") (name "unconnected-(U39-A0{slash}36{slash}VP-Pad3)") (class "Default")
      (node (ref "U39") (pin "3") (pinfunction "A0/36/VP_3") (pintype "bidirectional"))
    )
    (net (code "88") (name "unconnected-(U39-A3{slash}39{slash}VN-Pad4)") (class "Default")
      (node (ref "U39") (pin "4") (pinfunction "A3/39/VN_4") (pintype "bidirectional"))
    )
    (net (code "89") (name "unconnected-(U39-A4{slash}32-Pad5)") (class "Default")
      (node (ref "U39") (pin "5") (pinfunction "A4/32_5") (pintype "bidirectional"))
    )
    (net (code "90") (name "unconnected-(U39-A5{slash}33-Pad6)") (class "Default")
      (node (ref "U39") (pin "6") (pinfunction "A5/33_6") (pintype "bidirectional"))
    )
    (net (code "91") (name "unconnected-(U39-A6{slash}34-Pad7)") (class "Default")
      (node (ref "U39") (pin "7") (pinfunction "A6/34_7") (pintype "bidirectional"))
    )
    (net (code "92") (name "unconnected-(U39-A7{slash}35-Pad8)") (class "Default")
      (node (ref "U39") (pin "8") (pinfunction "A7/35_8") (pintype "bidirectional"))
    )
    (net (code "93") (name "unconnected-(U39-A14{slash}12-Pad13)") (class "Default")
      (node (ref "U39") (pin "13") (pinfunction "A14/12_13") (pintype "bidirectional"))
    )
    (net (code "94") (name "unconnected-(U39-A16{slash}14-Pad12)") (class "Default")
      (node (ref "U39") (pin "12") (pinfunction "A16/14_12") (pintype "bidirectional"))
    )
    (net (code "95") (name "unconnected-(U39-A17{slash}27-Pad11)") (class "Default")
      (node (ref "U39") (pin "11") (pinfunction "A17/27_11") (pintype "bidirectional"))
    )
    (net (code "96") (name "unconnected-(U39-A18{slash}DAC1{slash}25-Pad9)") (class "Default")
      (node (ref "U39") (pin "9") (pinfunction "A18/DAC1/25_9") (pintype "bidirectional"))
    )
    (net (code "97") (name "unconnected-(U39-A19{slash}DAC2{slash}26-Pad10)") (class "Default")
      (node (ref "U39") (pin "10") (pinfunction "A19/DAC2/26_10") (pintype "bidirectional"))
    )
    (net (code "98") (name "unconnected-(U39-ENABLE-Pad2)") (class "Default")
      (node (ref "U39") (pin "2") (pinfunction "ENABLE_2") (pintype "input"))
    )
    (net (code "99") (name "unconnected-(U39-GPIO_0-Pad32)") (class "Default")
      (node (ref "U39") (pin "32") (pinfunction "GPIO_0_32") (pintype "power_in"))
    )
    (net (code "100") (name "unconnected-(U39-GPIO_2-Pad34)") (class "Default")
      (node (ref "U39") (pin "34") (pinfunction "GPIO_2_34") (pintype "power_in"))
    )
    (net (code "101") (name "unconnected-(U39-GPIO_4-Pad31)") (class "Default")
      (node (ref "U39") (pin "31") (pinfunction "GPIO_4_31") (pintype "power_in"))
    )
    (net (code "102") (name "unconnected-(U39-GPIO_15-Pad35)") (class "Default")
      (node (ref "U39") (pin "35") (pinfunction "GPIO_15_35") (pintype "power_in"))
    )
    (net (code "103") (name "unconnected-(U39-GPIO_16-Pad30)") (class "Default")
      (node (ref "U39") (pin "30") (pinfunction "GPIO_16_30") (pintype "power_in"))
    )
    (net (code "104") (name "unconnected-(U39-GPIO_17-Pad29)") (class "Default")
      (node (ref "U39") (pin "29") (pinfunction "GPIO_17_29") (pintype "power_in"))
    )
    (net (code "105") (name "unconnected-(U39-MISO{slash}19-Pad24)") (class "Default")
      (node (ref "U39") (pin "24") (pinfunction "MISO/19_24") (pintype "power_in"))
    )
    (net (code "106") (name "unconnected-(U39-MOSI{slash}23-Pad25)") (class "Default")
      (node (ref "U39") (pin "25") (pinfunction "MOSI/23_25") (pintype "power_in"))
    )
    (net (code "107") (name "unconnected-(U39-RX{slash}2-Pad18)") (class "Default")
      (node (ref "U39") (pin "18") (pinfunction "RX/2_18") (pintype "power_in"))
    )
    (net (code "108") (name "unconnected-(U39-SCK{slash}18-Pad26)") (class "Default")
      (node (ref "U39") (pin "26") (pinfunction "SCK/18_26") (pintype "power_in"))
    )
    (net (code "109") (name "unconnected-(U39-SS{slash}5{slash}LED-Pad27)") (class "Default")
      (node (ref "U39") (pin "27") (pinfunction "SS/5/LED_27") (pintype "power_in"))
    )
    (net (code "110") (name "unconnected-(U39-TX{slash}1-Pad17)") (class "Default")
      (node (ref "U39") (pin "17") (pinfunction "TX/1_17") (pintype "power_in"))
    )
  )
)
